# tree.net
KiCad netlist of a schematic drawn in Altium Designer
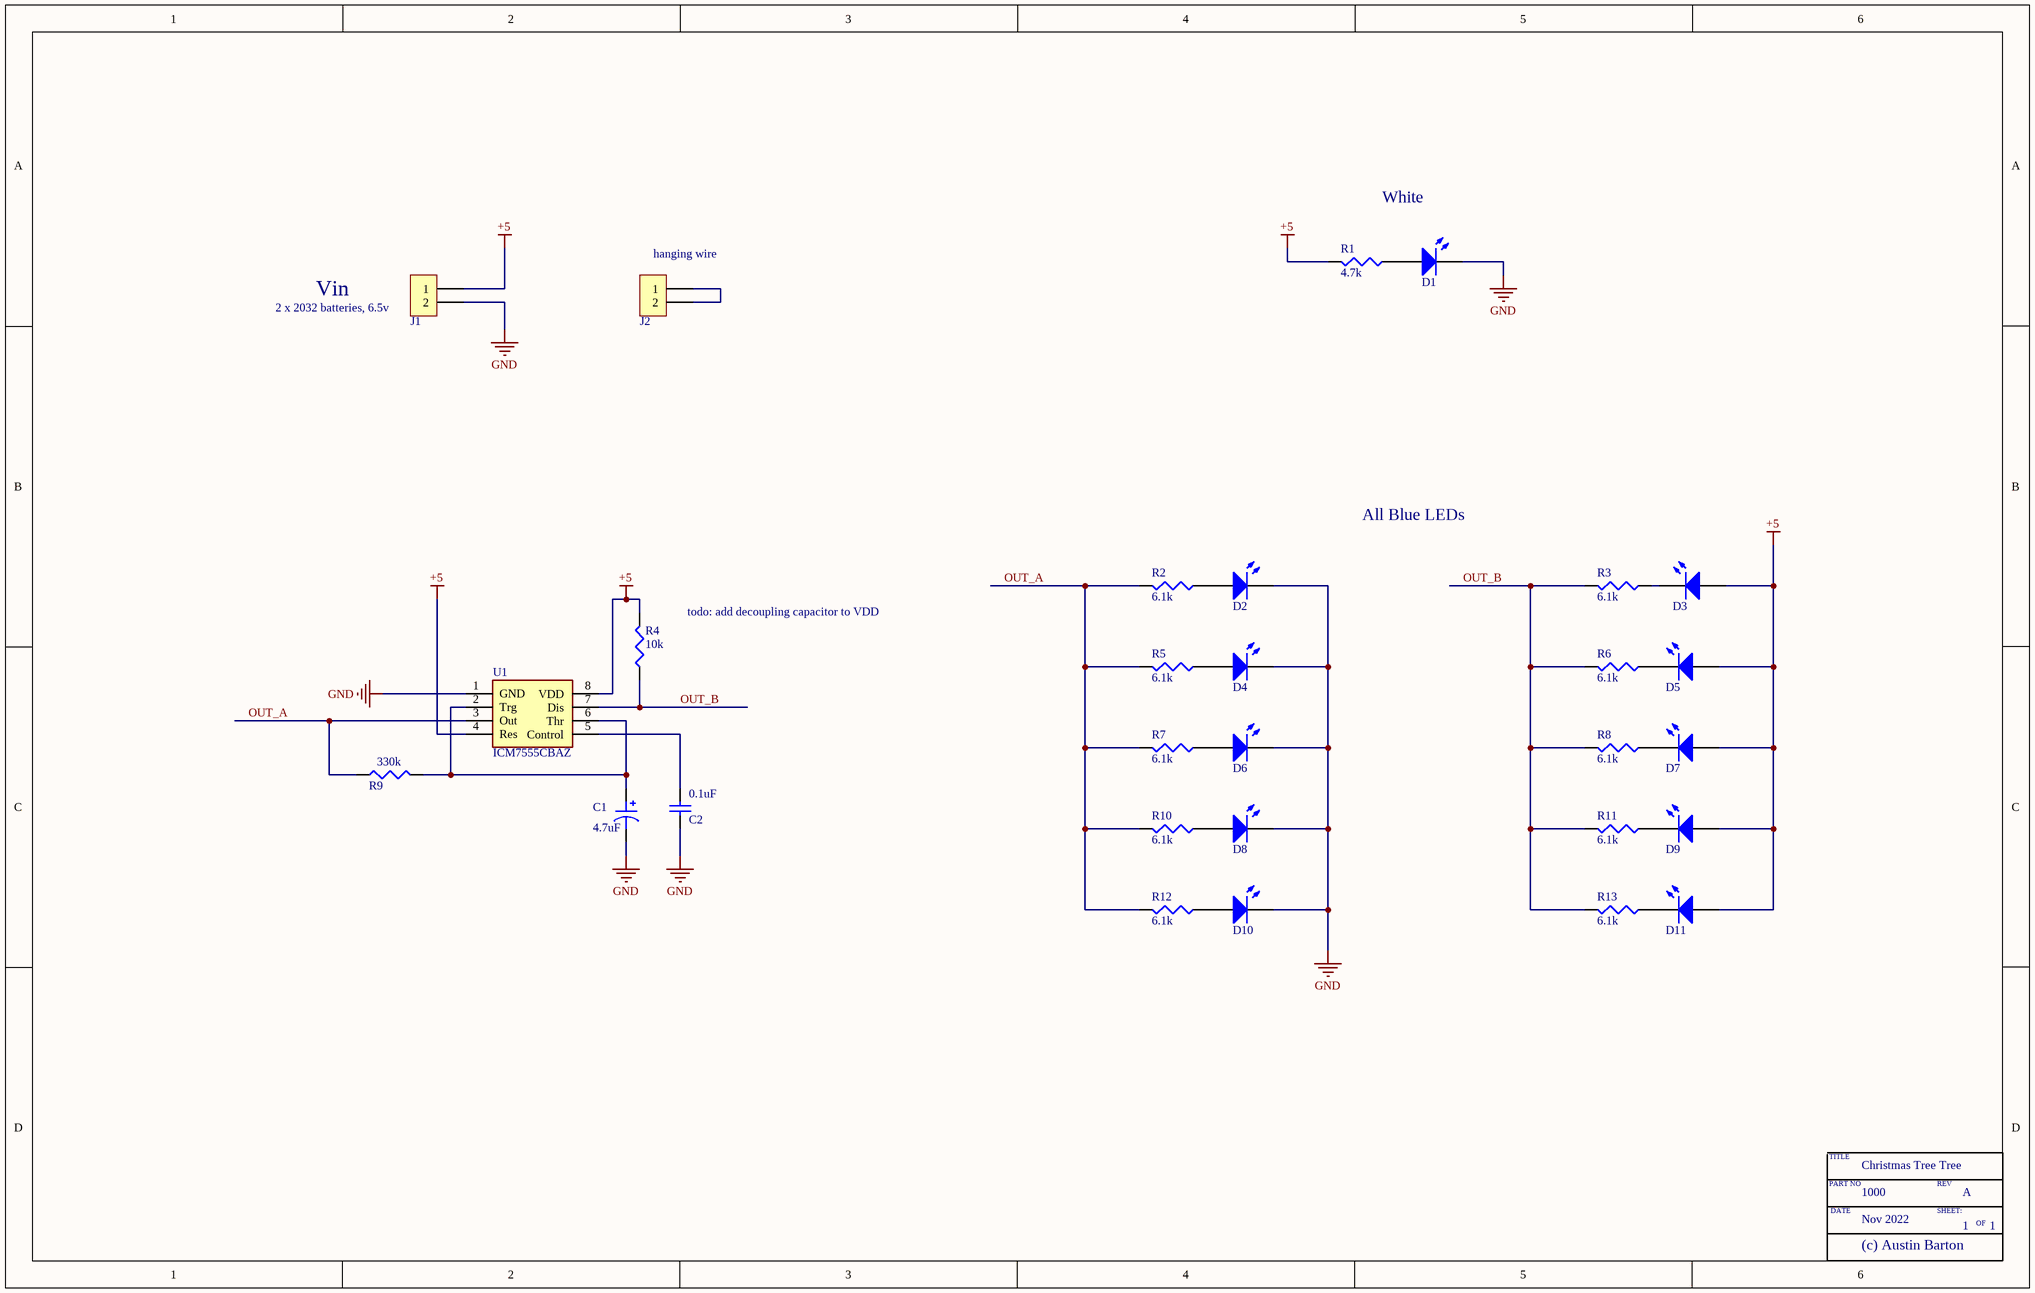
[diagram p0: tree.SchDoc]

(export (version "E")
  (design (tool "Eeschema 10.0.6"))
  (components
    (comp (ref "C1")
      (value "4.7uF")
      (footprint "th_cap")
      (description "SMT Polarised Capacitor")
      (libsource (lib "th_cap") (part "th_cap"))
    )
    (comp (ref "C2")
      (value "0.1uF")
      (footprint "CAPC2012X09M")
      (description "0.1pF 50V Ceramic Capacitor C0G, NP0 0805 (2012 Metric)")
      (fields (field (name "PART NUMBER") "C0805C180J5GACTU") (field (name "MANUFACTURER") "Kemet"))
      (libsource (lib "database") (part "Cap_Generic_Nonpolarized"))
    )
    (comp (ref "D1")
      (value "APT2012SURCK")
      (footprint "LED_0805_A_K")
      (description "LED RED CLEAR 0805 SMD")
      (fields (field (name "MANUFACTURER") "Kingbright"))
      (libsource (lib "database") (part "LED_A_K"))
    )
    (comp (ref "D2")
      (value "APT2012SURCK")
      (footprint "LED_0805_A_K")
      (description "LED RED CLEAR 0805 SMD")
      (fields (field (name "MANUFACTURER") "Kingbright"))
      (libsource (lib "database") (part "LED_A_K"))
    )
    (comp (ref "D3")
      (value "APT2012SURCK")
      (footprint "LED_0805_A_K")
      (description "LED RED CLEAR 0805 SMD")
      (fields (field (name "MANUFACTURER") "Kingbright"))
      (libsource (lib "database") (part "LED_A_K"))
    )
    (comp (ref "D4")
      (value "APT2012SURCK")
      (footprint "LED_0805_A_K")
      (description "LED RED CLEAR 0805 SMD")
      (fields (field (name "MANUFACTURER") "Kingbright"))
      (libsource (lib "database") (part "LED_A_K"))
    )
    (comp (ref "D5")
      (value "APT2012SURCK")
      (footprint "LED_0805_A_K")
      (description "LED RED CLEAR 0805 SMD")
      (fields (field (name "MANUFACTURER") "Kingbright"))
      (libsource (lib "database") (part "LED_A_K"))
    )
    (comp (ref "D6")
      (value "APT2012SURCK")
      (footprint "LED_0805_A_K")
      (description "LED RED CLEAR 0805 SMD")
      (fields (field (name "MANUFACTURER") "Kingbright"))
      (libsource (lib "database") (part "LED_A_K"))
    )
    (comp (ref "D7")
      (value "APT2012SURCK")
      (footprint "LED_0805_A_K")
      (description "LED RED CLEAR 0805 SMD")
      (fields (field (name "MANUFACTURER") "Kingbright"))
      (libsource (lib "database") (part "LED_A_K"))
    )
    (comp (ref "D8")
      (value "APT2012SURCK")
      (footprint "LED_0805_A_K")
      (description "LED RED CLEAR 0805 SMD")
      (fields (field (name "MANUFACTURER") "Kingbright"))
      (libsource (lib "database") (part "LED_A_K"))
    )
    (comp (ref "D9")
      (value "APT2012SURCK")
      (footprint "LED_0805_A_K")
      (description "LED RED CLEAR 0805 SMD")
      (fields (field (name "MANUFACTURER") "Kingbright"))
      (libsource (lib "database") (part "LED_A_K"))
    )
    (comp (ref "D10")
      (value "APT2012SURCK")
      (footprint "LED_0805_A_K")
      (description "LED RED CLEAR 0805 SMD")
      (fields (field (name "MANUFACTURER") "Kingbright"))
      (libsource (lib "database") (part "LED_A_K"))
    )
    (comp (ref "D11")
      (value "APT2012SURCK")
      (footprint "LED_0805_A_K")
      (description "LED RED CLEAR 0805 SMD")
      (fields (field (name "MANUFACTURER") "Kingbright"))
      (libsource (lib "database") (part "LED_A_K"))
    )
    (comp (ref "J1")
      (value "~")
      (footprint "th_cap")
      (description "2 PIN HEADER TIN")
      (libsource (lib "hdr1x2") (part "HDR1x2"))
    )
    (comp (ref "J2")
      (value "~")
      (footprint "th_cap")
      (description "2 PIN HEADER TIN")
      (libsource (lib "hdr1x2") (part "HDR1x2"))
    )
    (comp (ref "R1")
      (value "4.7k")
      (footprint "RESC2012X06L65")
      (description "RES SMD 1% 1/8W 0805")
      (fields (field (name "PART NUMBER") "RC0805FR-07120RL") (field (name "MANUFACTURER") "Yageo"))
      (libsource (lib "database") (part "Res_Generic"))
    )
    (comp (ref "R2")
      (value "6.1k")
      (footprint "RESC2012X06L65")
      (description "RES SMD 1% 1/8W 0805")
      (fields (field (name "PART NUMBER") "RC0805FR-07120RL") (field (name "MANUFACTURER") "Yageo"))
      (libsource (lib "database") (part "Res_Generic"))
    )
    (comp (ref "R3")
      (value "6.1k")
      (footprint "RESC2012X06L65")
      (description "RES SMD 1% 1/8W 0805")
      (fields (field (name "PART NUMBER") "RC0805FR-07120RL") (field (name "MANUFACTURER") "Yageo"))
      (libsource (lib "database") (part "Res_Generic"))
    )
    (comp (ref "R4")
      (value "10k")
      (footprint "RESC2012X06L65")
      (description "RES SMD 1% 1/8W 0805")
      (fields (field (name "PART NUMBER") "RC0805FR-07120RL") (field (name "MANUFACTURER") "Yageo"))
      (libsource (lib "database") (part "Res_Generic"))
    )
    (comp (ref "R5")
      (value "6.1k")
      (footprint "RESC2012X06L65")
      (description "RES SMD 1% 1/8W 0805")
      (fields (field (name "PART NUMBER") "RC0805FR-07120RL") (field (name "MANUFACTURER") "Yageo"))
      (libsource (lib "database") (part "Res_Generic"))
    )
    (comp (ref "R6")
      (value "6.1k")
      (footprint "RESC2012X06L65")
      (description "RES SMD 1% 1/8W 0805")
      (fields (field (name "PART NUMBER") "RC0805FR-07120RL") (field (name "MANUFACTURER") "Yageo"))
      (libsource (lib "database") (part "Res_Generic"))
    )
    (comp (ref "R7")
      (value "6.1k")
      (footprint "RESC2012X06L65")
      (description "RES SMD 1% 1/8W 0805")
      (fields (field (name "PART NUMBER") "RC0805FR-07120RL") (field (name "MANUFACTURER") "Yageo"))
      (libsource (lib "database") (part "Res_Generic"))
    )
    (comp (ref "R8")
      (value "6.1k")
      (footprint "RESC2012X06L65")
      (description "RES SMD 1% 1/8W 0805")
      (fields (field (name "PART NUMBER") "RC0805FR-07120RL") (field (name "MANUFACTURER") "Yageo"))
      (libsource (lib "database") (part "Res_Generic"))
    )
    (comp (ref "R9")
      (value "330k")
      (footprint "RESC2012X06L65")
      (description "RES SMD 1% 1/8W 0805")
      (fields (field (name "PART NUMBER") "RC0805FR-07120RL") (field (name "MANUFACTURER") "Yageo"))
      (libsource (lib "database") (part "Res_Generic"))
    )
    (comp (ref "R10")
      (value "6.1k")
      (footprint "RESC2012X06L65")
      (description "RES SMD 1% 1/8W 0805")
      (fields (field (name "PART NUMBER") "RC0805FR-07120RL") (field (name "MANUFACTURER") "Yageo"))
      (libsource (lib "database") (part "Res_Generic"))
    )
    (comp (ref "R11")
      (value "6.1k")
      (footprint "RESC2012X06L65")
      (description "RES SMD 1% 1/8W 0805")
      (fields (field (name "PART NUMBER") "RC0805FR-07120RL") (field (name "MANUFACTURER") "Yageo"))
      (libsource (lib "database") (part "Res_Generic"))
    )
    (comp (ref "R12")
      (value "6.1k")
      (footprint "RESC2012X06L65")
      (description "RES SMD 1% 1/8W 0805")
      (fields (field (name "PART NUMBER") "RC0805FR-07120RL") (field (name "MANUFACTURER") "Yageo"))
      (libsource (lib "database") (part "Res_Generic"))
    )
    (comp (ref "R13")
      (value "6.1k")
      (footprint "RESC2012X06L65")
      (description "RES SMD 1% 1/8W 0805")
      (fields (field (name "PART NUMBER") "RC0805FR-07120RL") (field (name "MANUFACTURER") "Yageo"))
      (libsource (lib "database") (part "Res_Generic"))
    )
    (comp (ref "U1")
      (value "ICM7555CBAZ")
      (footprint "ICM7555CBAZ")
      (description "Timers & Support Products GEN PURPSE CMOS TIMR COM")
      (fields (field (name "MP") "USB-A1VSB6") (field (name "MF") "On Shore"))
      (libsource (lib "ICM7555CBAZ") (part "ICM7555CBAZ"))
    )
  )
  (nets
    (net (code "1") (name "+5") (class "Default")
      (node (ref "D11") (pin "1") (pinfunction "A_1") (pintype "passive"))
      (node (ref "D3") (pin "1") (pinfunction "A_1") (pintype "passive"))
      (node (ref "D5") (pin "1") (pinfunction "A_1") (pintype "passive"))
      (node (ref "D7") (pin "1") (pinfunction "A_1") (pintype "passive"))
      (node (ref "D9") (pin "1") (pinfunction "A_1") (pintype "passive"))
      (node (ref "J1") (pin "1") (pinfunction "1_1") (pintype "passive"))
      (node (ref "R1") (pin "2") (pinfunction "2_2") (pintype "passive"))
      (node (ref "R4") (pin "2") (pinfunction "2_2") (pintype "passive"))
      (node (ref "U1") (pin "4") (pinfunction "Res_4") (pintype "passive"))
      (node (ref "U1") (pin "8") (pinfunction "VDD_8") (pintype "passive"))
    )
    (net (code "2") (name "/OUT_A") (class "Default")
      (node (ref "R10") (pin "2") (pinfunction "2_2") (pintype "passive"))
      (node (ref "R12") (pin "2") (pinfunction "2_2") (pintype "passive"))
      (node (ref "R2") (pin "2") (pinfunction "2_2") (pintype "passive"))
      (node (ref "R5") (pin "2") (pinfunction "2_2") (pintype "passive"))
      (node (ref "R7") (pin "2") (pinfunction "2_2") (pintype "passive"))
      (node (ref "R9") (pin "1") (pinfunction "1_1") (pintype "passive"))
      (node (ref "U1") (pin "3") (pinfunction "Out_3") (pintype "passive"))
    )
    (net (code "3") (name "/OUT_B") (class "Default")
      (node (ref "R11") (pin "2") (pinfunction "2_2") (pintype "passive"))
      (node (ref "R13") (pin "2") (pinfunction "2_2") (pintype "passive"))
      (node (ref "R3") (pin "2") (pinfunction "2_2") (pintype "passive"))
      (node (ref "R4") (pin "1") (pinfunction "1_1") (pintype "passive"))
      (node (ref "R6") (pin "2") (pinfunction "2_2") (pintype "passive"))
      (node (ref "R8") (pin "2") (pinfunction "2_2") (pintype "passive"))
      (node (ref "U1") (pin "7") (pinfunction "Dis_7") (pintype "passive"))
    )
    (net (code "4") (name "GND") (class "Default")
      (node (ref "C1") (pin "2") (pinfunction "2_2") (pintype "passive"))
      (node (ref "C2") (pin "1") (pinfunction "1_1") (pintype "passive"))
      (node (ref "D1") (pin "2") (pinfunction "K_2") (pintype "passive"))
      (node (ref "D10") (pin "2") (pinfunction "K_2") (pintype "passive"))
      (node (ref "D2") (pin "2") (pinfunction "K_2") (pintype "passive"))
      (node (ref "D4") (pin "2") (pinfunction "K_2") (pintype "passive"))
      (node (ref "D6") (pin "2") (pinfunction "K_2") (pintype "passive"))
      (node (ref "D8") (pin "2") (pinfunction "K_2") (pintype "passive"))
      (node (ref "J1") (pin "2") (pinfunction "2_2") (pintype "passive"))
      (node (ref "U1") (pin "1") (pinfunction "GND_1") (pintype "passive"))
    )
    (net (code "5") (name "Net-(D1-A)") (class "Default")
      (node (ref "D1") (pin "1") (pinfunction "A_1") (pintype "passive"))
      (node (ref "R1") (pin "1") (pinfunction "1_1") (pintype "passive"))
    )
    (net (code "6") (name "Net-(D2-A)") (class "Default")
      (node (ref "D2") (pin "1") (pinfunction "A_1") (pintype "passive"))
      (node (ref "R2") (pin "1") (pinfunction "1_1") (pintype "passive"))
    )
    (net (code "7") (name "Net-(D3-K)") (class "Default")
      (node (ref "D3") (pin "2") (pinfunction "K_2") (pintype "passive"))
      (node (ref "R3") (pin "1") (pinfunction "1_1") (pintype "passive"))
    )
    (net (code "8") (name "Net-(D4-A)") (class "Default")
      (node (ref "D4") (pin "1") (pinfunction "A_1") (pintype "passive"))
      (node (ref "R5") (pin "1") (pinfunction "1_1") (pintype "passive"))
    )
    (net (code "9") (name "Net-(D5-K)") (class "Default")
      (node (ref "D5") (pin "2") (pinfunction "K_2") (pintype "passive"))
      (node (ref "R6") (pin "1") (pinfunction "1_1") (pintype "passive"))
    )
    (net (code "10") (name "Net-(D6-A)") (class "Default")
      (node (ref "D6") (pin "1") (pinfunction "A_1") (pintype "passive"))
      (node (ref "R7") (pin "1") (pinfunction "1_1") (pintype "passive"))
    )
    (net (code "11") (name "Net-(D7-K)") (class "Default")
      (node (ref "D7") (pin "2") (pinfunction "K_2") (pintype "passive"))
      (node (ref "R8") (pin "1") (pinfunction "1_1") (pintype "passive"))
    )
    (net (code "12") (name "Net-(D8-A)") (class "Default")
      (node (ref "D8") (pin "1") (pinfunction "A_1") (pintype "passive"))
      (node (ref "R10") (pin "1") (pinfunction "1_1") (pintype "passive"))
    )
    (net (code "13") (name "Net-(D9-K)") (class "Default")
      (node (ref "D9") (pin "2") (pinfunction "K_2") (pintype "passive"))
      (node (ref "R11") (pin "1") (pinfunction "1_1") (pintype "passive"))
    )
    (net (code "14") (name "Net-(D10-A)") (class "Default")
      (node (ref "D10") (pin "1") (pinfunction "A_1") (pintype "passive"))
      (node (ref "R12") (pin "1") (pinfunction "1_1") (pintype "passive"))
    )
    (net (code "15") (name "Net-(D11-K)") (class "Default")
      (node (ref "D11") (pin "2") (pinfunction "K_2") (pintype "passive"))
      (node (ref "R13") (pin "1") (pinfunction "1_1") (pintype "passive"))
    )
    (net (code "16") (name "Net-(J2-Pad1)") (class "Default")
      (node (ref "J2") (pin "1") (pinfunction "1_1") (pintype "passive"))
      (node (ref "J2") (pin "2") (pinfunction "2_2") (pintype "passive"))
    )
    (net (code "17") (name "Net-(U1-Control)") (class "Default")
      (node (ref "C2") (pin "2") (pinfunction "2_2") (pintype "passive"))
      (node (ref "U1") (pin "5") (pinfunction "Control_5") (pintype "passive"))
    )
    (net (code "18") (name "Net-(U1-Thr)") (class "Default")
      (node (ref "C1") (pin "1") (pinfunction "1_1") (pintype "passive"))
      (node (ref "R9") (pin "2") (pinfunction "2_2") (pintype "passive"))
      (node (ref "U1") (pin "2") (pinfunction "Trg_2") (pintype "passive"))
      (node (ref "U1") (pin "6") (pinfunction "Thr_6") (pintype "passive"))
    )
  )
)
